# cm_ltc6102.net
KiCad netlist of a schematic drawn in EAGLE
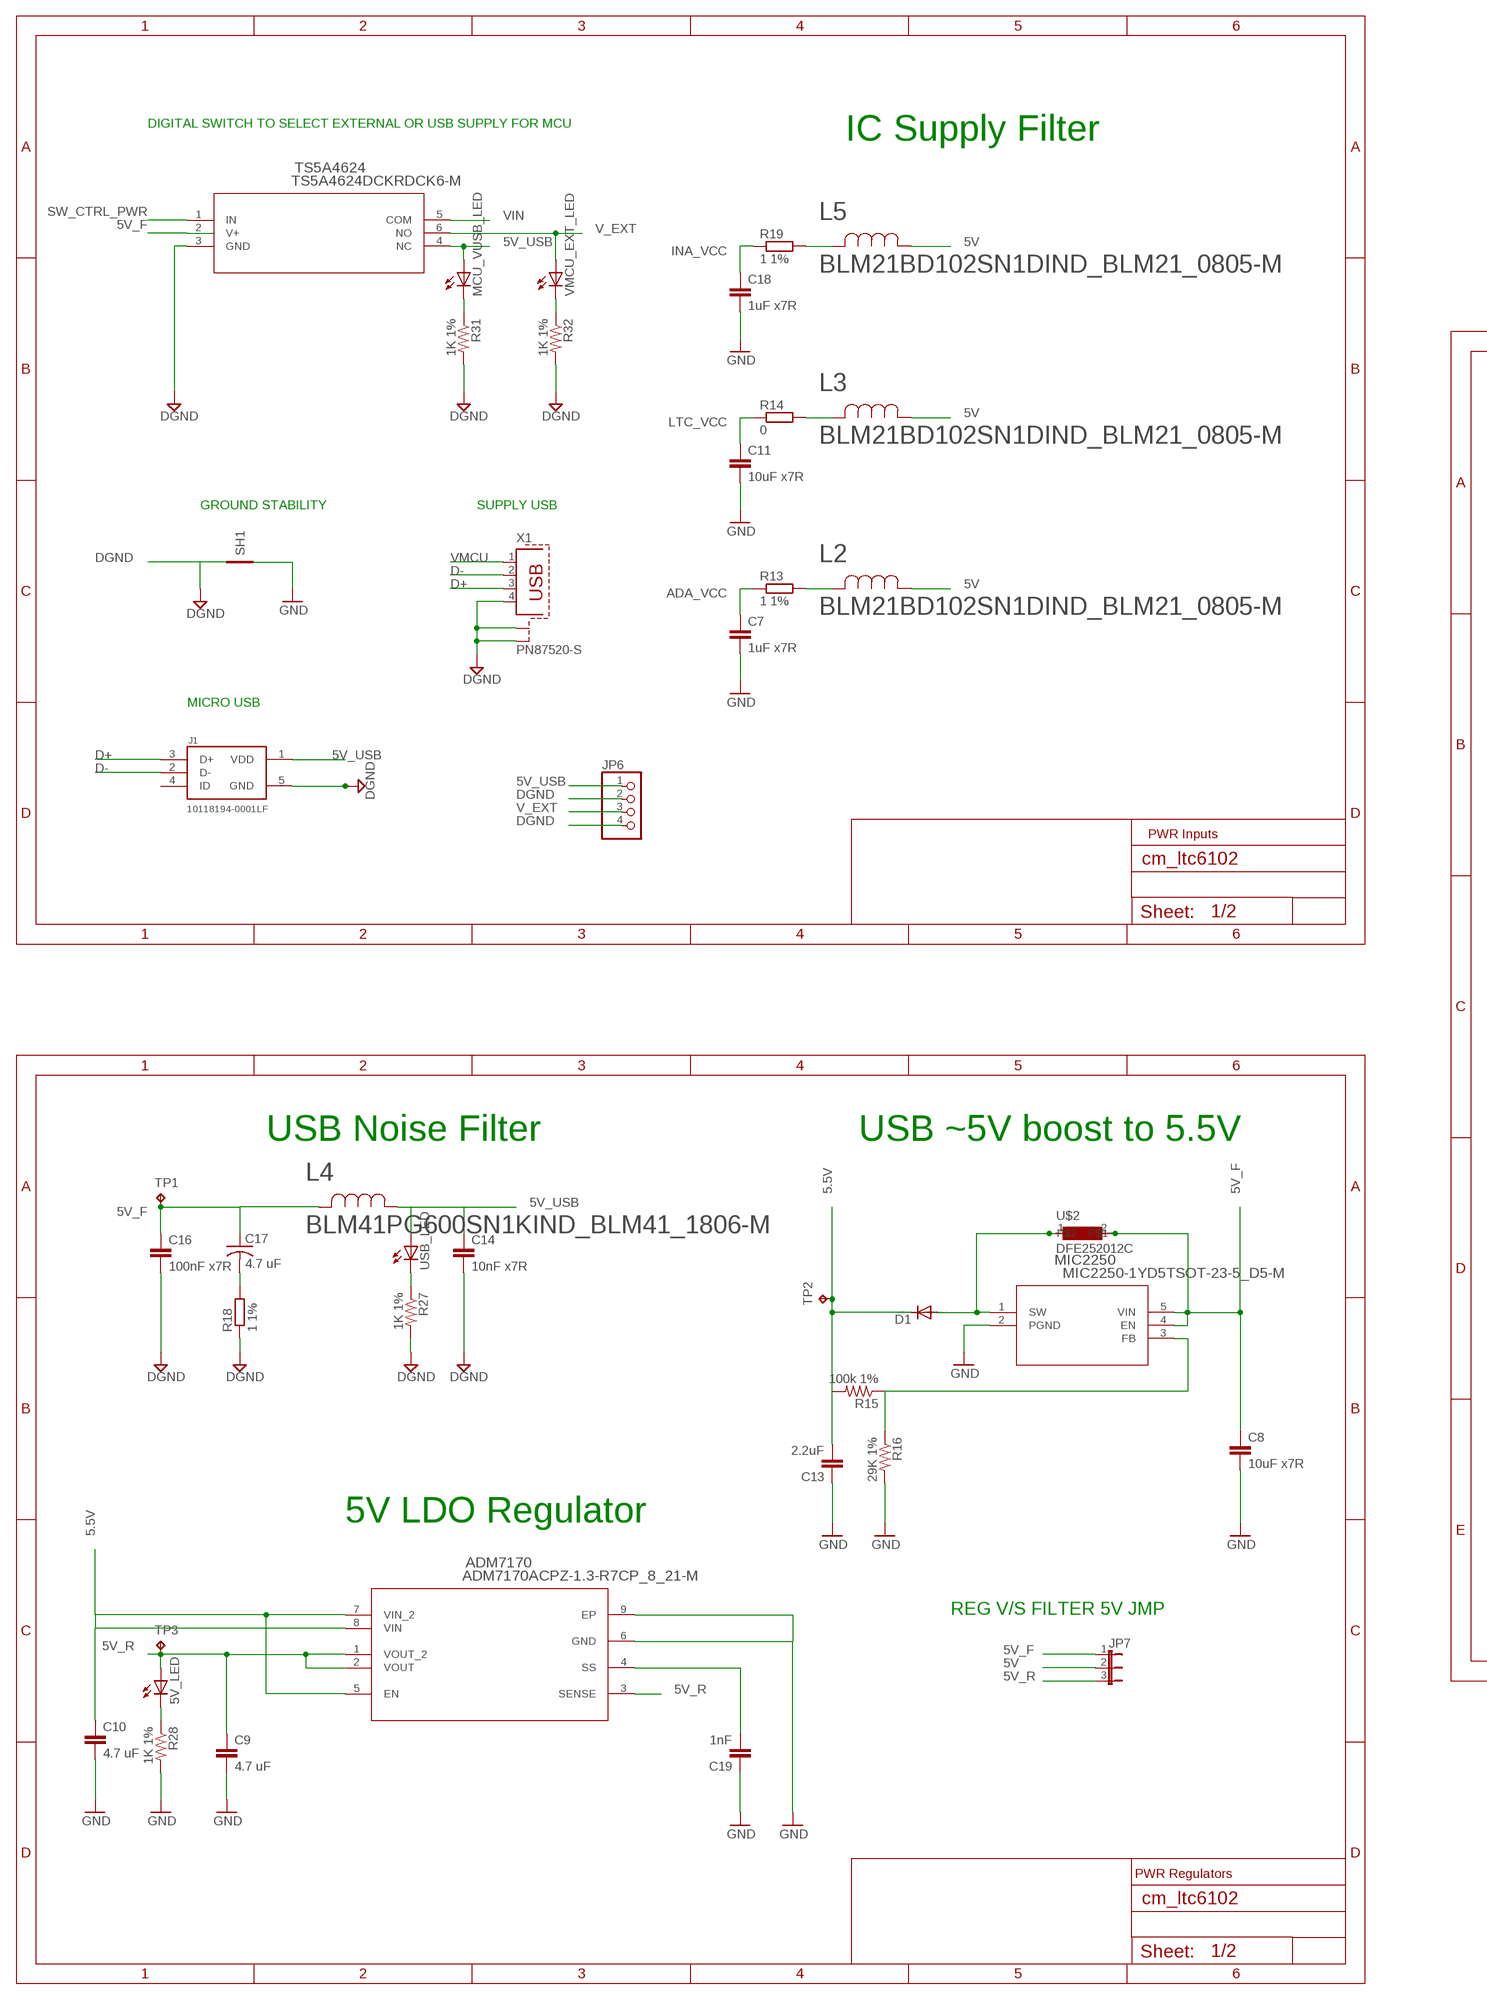
[diagram p0: schematic, sheet 1, part 1 of 2]
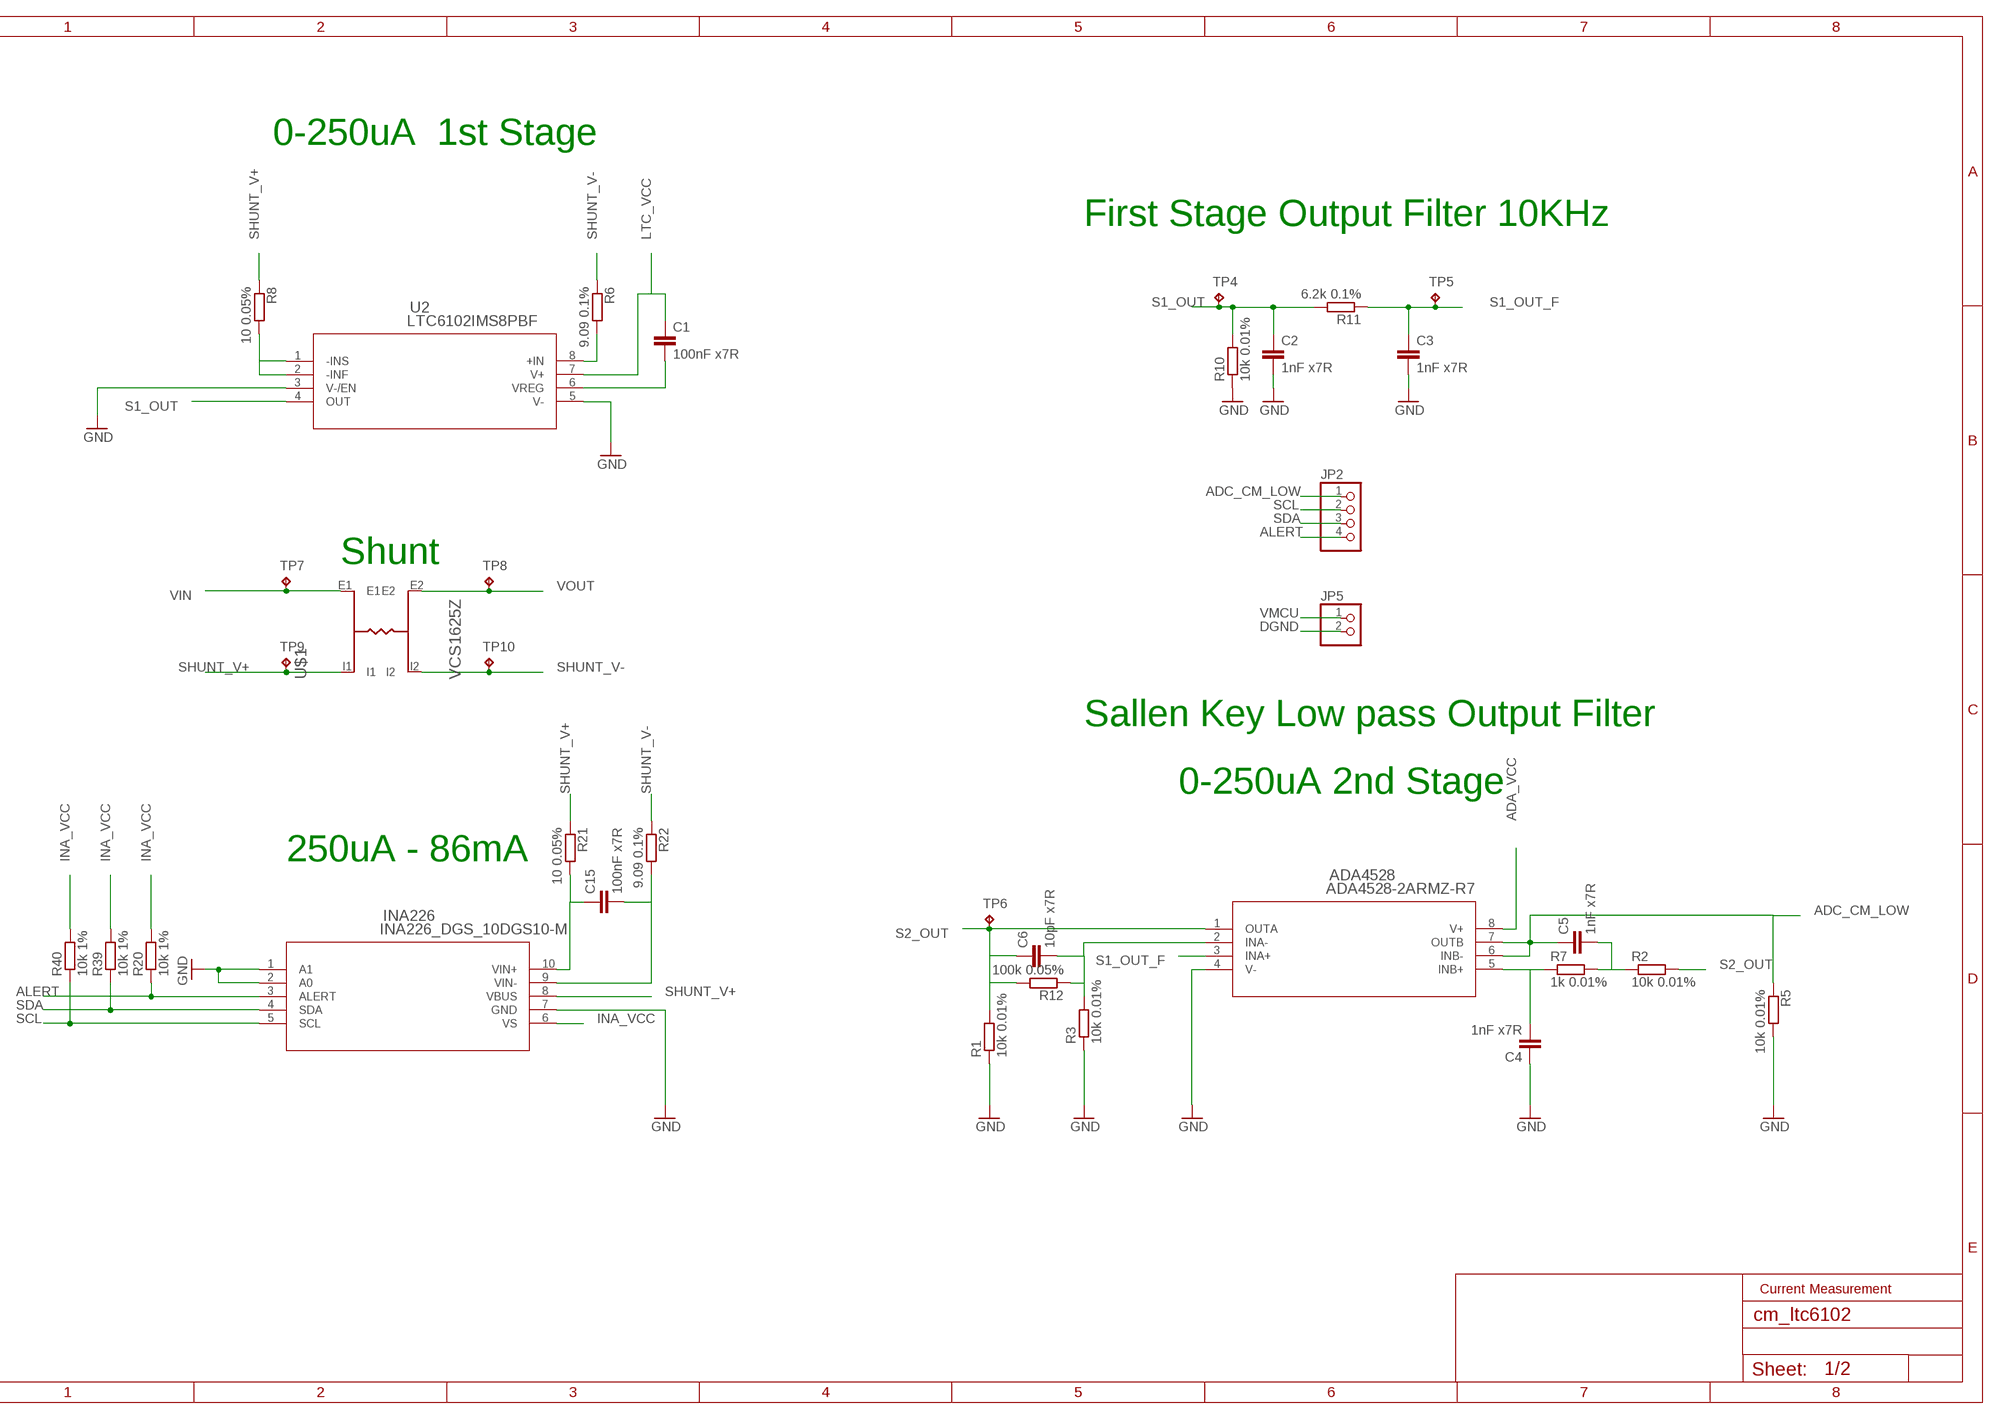
[diagram p1: schematic, sheet 1, part 2 of 2]
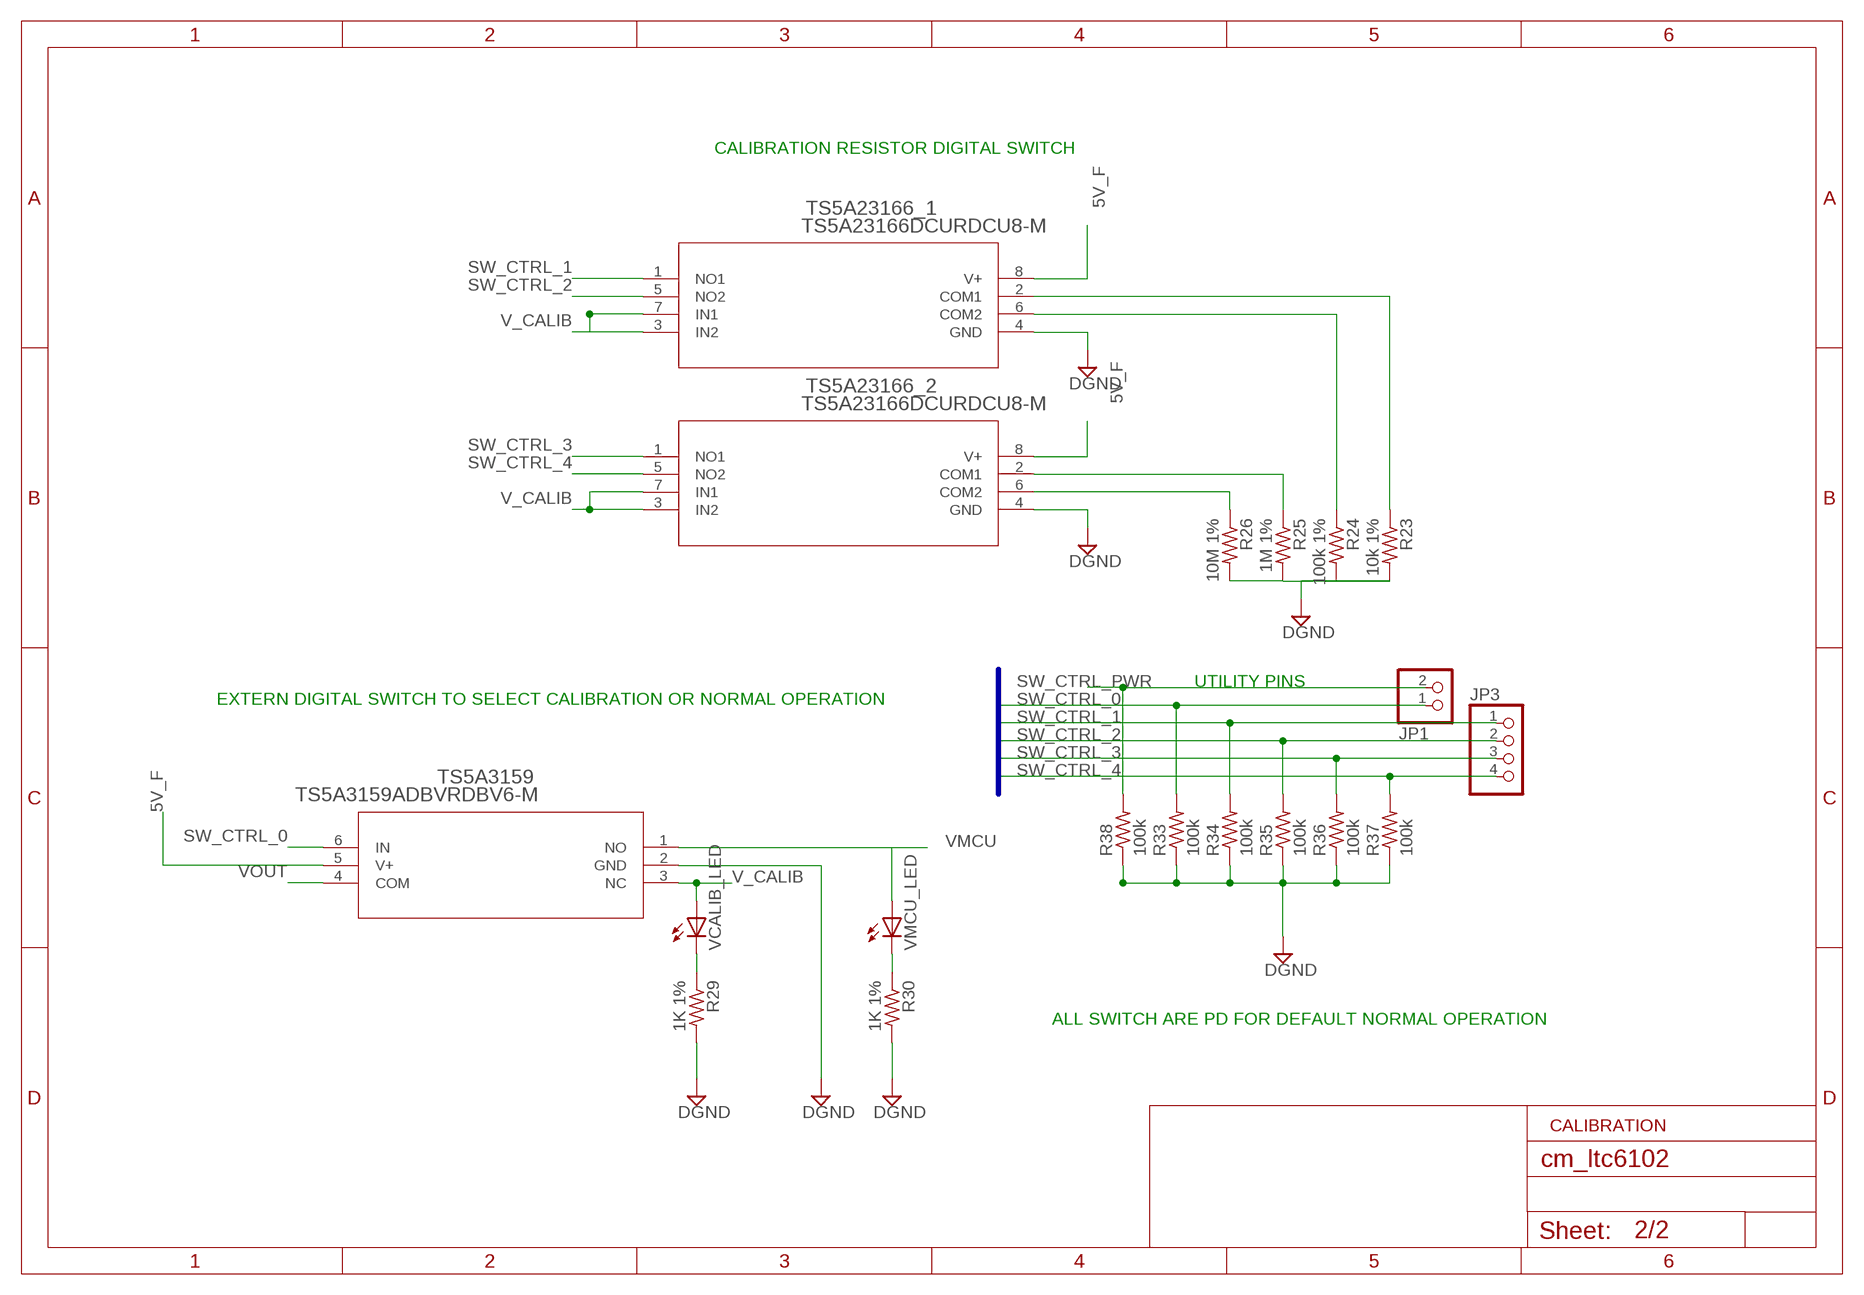
[diagram p2: schematic, sheet 2]

(export (version "E")
  (design (tool "Eeschema 10.0.6"))
  (components
    (comp (ref "5V_LED")
      (value "LEDCHIPLED_0603")
      (footprint "eagle-import:CHIPLED_0603")
      (libsource (lib "eagle-import") (part "LEDCHIPLED_0603"))
    )
    (comp (ref "ADA4528")
      (value "ADA4528-2ARMZ-R7")
      (footprint "eagle-import:RM_8")
      (fields (field (name "MANUFACTURER_PART_NUMBER") "ADA45282ARMZR7"))
      (libsource (lib "eagle-import") (part "ADA4528-2ARMZ-R7"))
    )
    (comp (ref "ADM7170")
      (value "ADM7170ACPZ-1.3-R7CP_8_21-M")
      (footprint "eagle-import:CP_8_21-M")
      (fields (field (name "MANUFACTURER_PART_NUMBER") "ADM7170ACPZ1.3R7"))
      (libsource (lib "eagle-import") (part "ADM7170ACPZ-1.3-R7CP_8_21-M"))
    )
    (comp (ref "C1")
      (value "100nF x7R")
      (footprint "eagle-import:C0603")
      (libsource (lib "eagle-import") (part "C-EUC0603"))
    )
    (comp (ref "C2")
      (value "1nF x7R")
      (footprint "eagle-import:C0603")
      (libsource (lib "eagle-import") (part "C-EUC0603"))
    )
    (comp (ref "C3")
      (value "1nF x7R")
      (footprint "eagle-import:C0603")
      (libsource (lib "eagle-import") (part "C-EUC0603"))
    )
    (comp (ref "C4")
      (value "1nF x7R")
      (footprint "eagle-import:C0603")
      (libsource (lib "eagle-import") (part "C-EUC0603"))
    )
    (comp (ref "C5")
      (value "1nF x7R")
      (footprint "eagle-import:C0603")
      (libsource (lib "eagle-import") (part "C-EUC0603"))
    )
    (comp (ref "C6")
      (value "10pF x7R")
      (footprint "eagle-import:C0603")
      (libsource (lib "eagle-import") (part "C-EUC0603"))
    )
    (comp (ref "C7")
      (value "1uF x7R")
      (footprint "eagle-import:C0603")
      (libsource (lib "eagle-import") (part "C-EUC0603"))
    )
    (comp (ref "C8")
      (value "10uF x7R")
      (footprint "eagle-import:C0805")
      (libsource (lib "eagle-import") (part "C-EUC0805"))
    )
    (comp (ref "C9")
      (value "4.7 uF")
      (footprint "eagle-import:C1206")
      (libsource (lib "eagle-import") (part "C-EUC1206"))
    )
    (comp (ref "C10")
      (value "4.7 uF")
      (footprint "eagle-import:C1206")
      (libsource (lib "eagle-import") (part "C-EUC1206"))
    )
    (comp (ref "C11")
      (value "10uF x7R")
      (footprint "eagle-import:C0805")
      (libsource (lib "eagle-import") (part "C-EUC0805"))
    )
    (comp (ref "C13")
      (value "2.2uF")
      (footprint "eagle-import:C0603")
      (libsource (lib "eagle-import") (part "C-EUC0603"))
    )
    (comp (ref "C14")
      (value "10nF x7R")
      (footprint "eagle-import:C0603")
      (libsource (lib "eagle-import") (part "C-EUC0603"))
    )
    (comp (ref "C15")
      (value "100nF x7R")
      (footprint "eagle-import:C0603")
      (libsource (lib "eagle-import") (part "C-EUC0603"))
    )
    (comp (ref "C16")
      (value "100nF x7R")
      (footprint "eagle-import:C0603")
      (libsource (lib "eagle-import") (part "C-EUC0603"))
    )
    (comp (ref "C17")
      (value "4.7 uF")
      (footprint "eagle-import:C1206")
      (libsource (lib "eagle-import") (part "C-USC1206"))
    )
    (comp (ref "C18")
      (value "1uF x7R")
      (footprint "eagle-import:C0603")
      (libsource (lib "eagle-import") (part "C-EUC0603"))
    )
    (comp (ref "C19")
      (value "1nF")
      (footprint "eagle-import:C0603")
      (libsource (lib "eagle-import") (part "C-EUC0603"))
    )
    (comp (ref "D1")
      (value "DIODE-SOD80C")
      (footprint "eagle-import:SOD80C")
      (libsource (lib "eagle-import") (part "DIODE-SOD80C"))
    )
    (comp (ref "INA226")
      (value "INA226_DGS_10DGS10-M")
      (footprint "eagle-import:DGS10-M")
      (fields (field (name "MANUFACTURER_PART_NUMBER") "INA226_DGS_10"))
      (libsource (lib "eagle-import") (part "INA226_DGS_10DGS10-M"))
    )
    (comp (ref "J1")
      (value "10118194-0001LF")
      (footprint "eagle-import:FRAMATOME_10118194-0001LF")
      (fields (field (name "MF") "Amphenol"))
      (libsource (lib "eagle-import") (part "10118194-0001LF"))
    )
    (comp (ref "JP2")
      (value "PINHD-1X4")
      (footprint "eagle-import:1X04")
      (libsource (lib "eagle-import") (part "PINHD-1X4"))
    )
    (comp (ref "JP5")
      (value "PINHD-1X2")
      (footprint "eagle-import:1X02")
      (libsource (lib "eagle-import") (part "PINHD-1X2"))
    )
    (comp (ref "JP6")
      (value "PINHD-1X4")
      (footprint "eagle-import:1X04")
      (libsource (lib "eagle-import") (part "PINHD-1X4"))
    )
    (comp (ref "JP7")
      (value "JP2E")
      (footprint "eagle-import:JP2")
      (libsource (lib "eagle-import") (part "JP2E"))
    )
    (comp (ref "L2")
      (value "BLM21BD102SN1DIND_BLM21_0805-M")
      (footprint "eagle-import:IND_BLM21_0805-M")
      (fields (field (name "MANUFACTURER_PART_NUMBER") "BLM21BD102SN1D"))
      (libsource (lib "eagle-import") (part "BLM21BD102SN1DIND_BLM21_0805-M"))
    )
    (comp (ref "L3")
      (value "BLM21BD102SN1DIND_BLM21_0805-M")
      (footprint "eagle-import:IND_BLM21_0805-M")
      (fields (field (name "MANUFACTURER_PART_NUMBER") "BLM21BD102SN1D"))
      (libsource (lib "eagle-import") (part "BLM21BD102SN1DIND_BLM21_0805-M"))
    )
    (comp (ref "L4")
      (value "BLM41PG600SN1KIND_BLM41_1806-M")
      (footprint "eagle-import:IND_BLM41_1806-M")
      (fields (field (name "MANUFACTURER_PART_NUMBER") "BLM41PG600SN1K"))
      (libsource (lib "eagle-import") (part "BLM41PG600SN1KIND_BLM41_1806-M"))
    )
    (comp (ref "L5")
      (value "BLM21BD102SN1DIND_BLM21_0805-M")
      (footprint "eagle-import:IND_BLM21_0805-M")
      (fields (field (name "MANUFACTURER_PART_NUMBER") "BLM21BD102SN1D"))
      (libsource (lib "eagle-import") (part "BLM21BD102SN1DIND_BLM21_0805-M"))
    )
    (comp (ref "MCU_VUSB_LED")
      (value "LEDCHIPLED_0603")
      (footprint "eagle-import:CHIPLED_0603")
      (libsource (lib "eagle-import") (part "LEDCHIPLED_0603"))
    )
    (comp (ref "MIC2250")
      (value "MIC2250-1YD5TSOT-23-5_D5-M")
      (footprint "eagle-import:TSOT-23-5_D5-M")
      (fields (field (name "MANUFACTURER_PART_NUMBER") "MIC22501YD5"))
      (libsource (lib "eagle-import") (part "MIC2250-1YD5TSOT-23-5_D5-M"))
    )
    (comp (ref "R1")
      (value "10k 0.01%")
      (footprint "eagle-import:R0603")
      (libsource (lib "eagle-import") (part "R-EU_R0603"))
    )
    (comp (ref "R2")
      (value "10k 0.01%")
      (footprint "eagle-import:R0603")
      (libsource (lib "eagle-import") (part "R-EU_R0603"))
    )
    (comp (ref "R3")
      (value "10k 0.01%")
      (footprint "eagle-import:R0603")
      (libsource (lib "eagle-import") (part "R-EU_R0603"))
    )
    (comp (ref "R5")
      (value "10k 0.01%")
      (footprint "eagle-import:R0603")
      (libsource (lib "eagle-import") (part "R-EU_R0603"))
    )
    (comp (ref "R6")
      (value "9.09 0.1%")
      (footprint "eagle-import:R0603")
      (libsource (lib "eagle-import") (part "R-EU_R0603"))
    )
    (comp (ref "R7")
      (value "1k 0.01%")
      (footprint "eagle-import:R0805")
      (libsource (lib "eagle-import") (part "R-EU_R0805"))
    )
    (comp (ref "R8")
      (value "10 0.05%")
      (footprint "eagle-import:R0603")
      (libsource (lib "eagle-import") (part "R-EU_R0603"))
    )
    (comp (ref "R10")
      (value "10k 0.01%")
      (footprint "eagle-import:R0603")
      (libsource (lib "eagle-import") (part "R-EU_R0603"))
    )
    (comp (ref "R11")
      (value "6.2k 0.1%")
      (footprint "eagle-import:R0603")
      (libsource (lib "eagle-import") (part "R-EU_R0603"))
    )
    (comp (ref "R12")
      (value "100k 0.05%")
      (footprint "eagle-import:R0603")
      (libsource (lib "eagle-import") (part "R-EU_R0603"))
    )
    (comp (ref "R13")
      (value "1 1%")
      (footprint "eagle-import:R0603")
      (libsource (lib "eagle-import") (part "R-EU_R0603"))
    )
    (comp (ref "R14")
      (value "0")
      (footprint "eagle-import:R0603")
      (libsource (lib "eagle-import") (part "R-EU_R0603"))
    )
    (comp (ref "R15")
      (value "100k 1%")
      (footprint "eagle-import:R0603")
      (libsource (lib "eagle-import") (part "R-US_R0603"))
    )
    (comp (ref "R16")
      (value "29K 1%")
      (footprint "eagle-import:R0603")
      (libsource (lib "eagle-import") (part "R-US_R0603"))
    )
    (comp (ref "R18")
      (value "1 1%")
      (footprint "eagle-import:R0603")
      (libsource (lib "eagle-import") (part "R-EU_R0603"))
    )
    (comp (ref "R19")
      (value "1 1%")
      (footprint "eagle-import:R0603")
      (libsource (lib "eagle-import") (part "R-EU_R0603"))
    )
    (comp (ref "R20")
      (value "10k 1%")
      (footprint "eagle-import:R0603")
      (libsource (lib "eagle-import") (part "R-EU_R0603"))
    )
    (comp (ref "R21")
      (value "10 0.05%")
      (footprint "eagle-import:R0603")
      (libsource (lib "eagle-import") (part "R-EU_R0603"))
    )
    (comp (ref "R22")
      (value "9.09 0.1%")
      (footprint "eagle-import:R0603")
      (libsource (lib "eagle-import") (part "R-EU_R0603"))
    )
    (comp (ref "R27")
      (value "1K 1%")
      (footprint "eagle-import:R0603")
      (libsource (lib "eagle-import") (part "R-US_R0603"))
    )
    (comp (ref "R28")
      (value "1K 1%")
      (footprint "eagle-import:R0603")
      (libsource (lib "eagle-import") (part "R-US_R0603"))
    )
    (comp (ref "R31")
      (value "1K 1%")
      (footprint "eagle-import:R0603")
      (libsource (lib "eagle-import") (part "R-US_R0603"))
    )
    (comp (ref "R32")
      (value "1K 1%")
      (footprint "eagle-import:R0603")
      (libsource (lib "eagle-import") (part "R-US_R0603"))
    )
    (comp (ref "R39")
      (value "10k 1%")
      (footprint "eagle-import:R0603")
      (libsource (lib "eagle-import") (part "R-EU_R0603"))
    )
    (comp (ref "R40")
      (value "10k 1%")
      (footprint "eagle-import:R0603")
      (libsource (lib "eagle-import") (part "R-EU_R0603"))
    )
    (comp (ref "SH1")
      (value "SHORT-VT5")
      (footprint "eagle-import:SHORT_TOP-50")
      (libsource (lib "eagle-import") (part "SHORT-VT5"))
    )
    (comp (ref "TP1")
      (value "TPPAD1-20")
      (footprint "eagle-import:P1-20")
      (libsource (lib "eagle-import") (part "TPPAD1-20"))
    )
    (comp (ref "TP2")
      (value "TPPAD1-20")
      (footprint "eagle-import:P1-20")
      (libsource (lib "eagle-import") (part "TPPAD1-20"))
    )
    (comp (ref "TP3")
      (value "TPPAD1-20")
      (footprint "eagle-import:P1-20")
      (libsource (lib "eagle-import") (part "TPPAD1-20"))
    )
    (comp (ref "TP4")
      (value "TPPAD1-20")
      (footprint "eagle-import:P1-20")
      (libsource (lib "eagle-import") (part "TPPAD1-20"))
    )
    (comp (ref "TP5")
      (value "TPPAD1-20")
      (footprint "eagle-import:P1-20")
      (libsource (lib "eagle-import") (part "TPPAD1-20"))
    )
    (comp (ref "TP6")
      (value "TPPAD1-20")
      (footprint "eagle-import:P1-20")
      (libsource (lib "eagle-import") (part "TPPAD1-20"))
    )
    (comp (ref "TP7")
      (value "TPPAD1-20")
      (footprint "eagle-import:P1-20")
      (libsource (lib "eagle-import") (part "TPPAD1-20"))
    )
    (comp (ref "TP8")
      (value "TPPAD1-20")
      (footprint "eagle-import:P1-20")
      (libsource (lib "eagle-import") (part "TPPAD1-20"))
    )
    (comp (ref "TP9")
      (value "TPPAD1-20")
      (footprint "eagle-import:P1-20")
      (libsource (lib "eagle-import") (part "TPPAD1-20"))
    )
    (comp (ref "TP10")
      (value "TPPAD1-20")
      (footprint "eagle-import:P1-20")
      (libsource (lib "eagle-import") (part "TPPAD1-20"))
    )
    (comp (ref "TS5A4624")
      (value "TS5A4624DCKRDCK6-M")
      (footprint "eagle-import:DCK6-M")
      (fields (field (name "MANUFACTURER_PART_NUMBER") "TS5A4624DCKR"))
      (libsource (lib "eagle-import") (part "TS5A4624DCKRDCK6-M"))
    )
    (comp (ref "U$1")
      (value "VCS1625Z")
      (footprint "eagle-import:VCS1625Z")
      (libsource (lib "eagle-import") (part "VCS1625Z"))
    )
    (comp (ref "U$2")
      (value "DFE252012C")
      (footprint "eagle-import:DFE252012C")
      (libsource (lib "eagle-import") (part "DFE252012C"))
    )
    (comp (ref "U2")
      (value "LTC6102IMS8PBF")
      (footprint "eagle-import:MSOP-8_MS")
      (fields (field (name "MANUFACTURER_PART_NUMBER") "LTC6102IMS8#PBF"))
      (libsource (lib "eagle-import") (part "LTC6102IMS8PBF"))
    )
    (comp (ref "USB_LED")
      (value "LEDCHIPLED_0603")
      (footprint "eagle-import:CHIPLED_0603")
      (libsource (lib "eagle-import") (part "LEDCHIPLED_0603"))
    )
    (comp (ref "VMCU_EXT_LED")
      (value "LEDCHIPLED_0603")
      (footprint "eagle-import:CHIPLED_0603")
      (libsource (lib "eagle-import") (part "LEDCHIPLED_0603"))
    )
    (comp (ref "X1")
      (value "PN87520-S")
      (footprint "eagle-import:PN87520-S")
      (libsource (lib "eagle-import") (part "PN87520-S"))
    )
    (comp (ref "JP1")
      (value "PINHD-1X2")
      (footprint "eagle-import:1X02")
      (libsource (lib "eagle-import") (part "PINHD-1X2"))
    )
    (comp (ref "JP3")
      (value "PINHD-1X4")
      (footprint "eagle-import:1X04")
      (libsource (lib "eagle-import") (part "PINHD-1X4"))
    )
    (comp (ref "R23")
      (value "10k 1%")
      (footprint "eagle-import:R0603")
      (libsource (lib "eagle-import") (part "R-US_R0603"))
    )
    (comp (ref "R24")
      (value "100k 1%")
      (footprint "eagle-import:R0603")
      (libsource (lib "eagle-import") (part "R-US_R0603"))
    )
    (comp (ref "R25")
      (value "1M 1%")
      (footprint "eagle-import:R0603")
      (libsource (lib "eagle-import") (part "R-US_R0603"))
    )
    (comp (ref "R26")
      (value "10M 1%")
      (footprint "eagle-import:R0603")
      (libsource (lib "eagle-import") (part "R-US_R0603"))
    )
    (comp (ref "R29")
      (value "1K 1%")
      (footprint "eagle-import:R0603")
      (libsource (lib "eagle-import") (part "R-US_R0603"))
    )
    (comp (ref "R30")
      (value "1K 1%")
      (footprint "eagle-import:R0603")
      (libsource (lib "eagle-import") (part "R-US_R0603"))
    )
    (comp (ref "R33")
      (value "100k")
      (footprint "eagle-import:R0805")
      (libsource (lib "eagle-import") (part "resistor_348_R-US_R0805"))
    )
    (comp (ref "R34")
      (value "100k")
      (footprint "eagle-import:R0805")
      (libsource (lib "eagle-import") (part "resistor_348_R-US_R0805"))
    )
    (comp (ref "R35")
      (value "100k")
      (footprint "eagle-import:R0805")
      (libsource (lib "eagle-import") (part "resistor_348_R-US_R0805"))
    )
    (comp (ref "R36")
      (value "100k")
      (footprint "eagle-import:R0805")
      (libsource (lib "eagle-import") (part "resistor_348_R-US_R0805"))
    )
    (comp (ref "R37")
      (value "100k")
      (footprint "eagle-import:R0805")
      (libsource (lib "eagle-import") (part "resistor_348_R-US_R0805"))
    )
    (comp (ref "R38")
      (value "100k")
      (footprint "eagle-import:R0805")
      (libsource (lib "eagle-import") (part "resistor_348_R-US_R0805"))
    )
    (comp (ref "TS5A3159")
      (value "TS5A3159ADBVRDBV6-M")
      (footprint "eagle-import:DBV6-M")
      (fields (field (name "MANUFACTURER_PART_NUMBER") "TS5A3159ADBVR"))
      (libsource (lib "eagle-import") (part "TS5A3159ADBVRDBV6-M"))
    )
    (comp (ref "TS5A23166_1")
      (value "TS5A23166DCURDCU8-M")
      (footprint "eagle-import:DCU8-M")
      (fields (field (name "MANUFACTURER_PART_NUMBER") "TS5A23166DCUR"))
      (libsource (lib "eagle-import") (part "TS5A23166DCURDCU8-M"))
    )
    (comp (ref "TS5A23166_2")
      (value "TS5A23166DCURDCU8-M")
      (footprint "eagle-import:DCU8-M")
      (fields (field (name "MANUFACTURER_PART_NUMBER") "TS5A23166DCUR"))
      (libsource (lib "eagle-import") (part "TS5A23166DCURDCU8-M"))
    )
    (comp (ref "VCALIB_LED")
      (value "LEDCHIPLED_0603")
      (footprint "eagle-import:CHIPLED_0603")
      (libsource (lib "eagle-import") (part "LEDCHIPLED_0603"))
    )
    (comp (ref "VMCU_LED")
      (value "LEDCHIPLED_0603")
      (footprint "eagle-import:CHIPLED_0603")
      (libsource (lib "eagle-import") (part "LEDCHIPLED_0603"))
    )
  )
  (nets
    (net (code "1") (name "5.5V") (class "Default")
      (node (ref "ADM7170") (pin "5") (pinfunction "EN_5") (pintype "passive"))
      (node (ref "ADM7170") (pin "7") (pinfunction "VIN_2_7") (pintype "passive"))
      (node (ref "ADM7170") (pin "8") (pinfunction "VIN_8") (pintype "passive"))
      (node (ref "C10") (pin "1") (pinfunction "1_1") (pintype "passive"))
      (node (ref "C13") (pin "2") (pinfunction "2_2") (pintype "passive"))
      (node (ref "D1") (pin "C") (pinfunction "C_C") (pintype "passive"))
      (node (ref "R15") (pin "2") (pinfunction "2_2") (pintype "passive"))
      (node (ref "TP2") (pin "TP") (pinfunction "TP_TP") (pintype "input"))
    )
    (net (code "2") (name "5V") (class "Default")
      (node (ref "JP7") (pin "2") (pinfunction "2_2") (pintype "passive"))
      (node (ref "L2") (pin "1") (pinfunction "1_1") (pintype "passive"))
      (node (ref "L3") (pin "1") (pinfunction "1_1") (pintype "passive"))
      (node (ref "L5") (pin "1") (pinfunction "1_1") (pintype "passive"))
    )
    (net (code "3") (name "5V_F") (class "Default")
      (node (ref "C16") (pin "1") (pinfunction "1_1") (pintype "passive"))
      (node (ref "C17") (pin "1") (pinfunction "1_1") (pintype "passive"))
      (node (ref "C8") (pin "1") (pinfunction "1_1") (pintype "passive"))
      (node (ref "JP7") (pin "1") (pinfunction "1_1") (pintype "passive"))
      (node (ref "L4") (pin "2") (pinfunction "2_2") (pintype "passive"))
      (node (ref "MIC2250") (pin "4") (pinfunction "EN_4") (pintype "input"))
      (node (ref "MIC2250") (pin "5") (pinfunction "VIN_5") (pintype "input"))
      (node (ref "TP1") (pin "TP") (pinfunction "TP_TP") (pintype "input"))
      (node (ref "TS5A23166_1") (pin "8") (pinfunction "V+_8") (pintype "passive"))
      (node (ref "TS5A23166_2") (pin "8") (pinfunction "V+_8") (pintype "passive"))
      (node (ref "TS5A3159") (pin "5") (pinfunction "V+_5") (pintype "power_in"))
      (node (ref "TS5A4624") (pin "2") (pinfunction "V+_2") (pintype "power_in"))
      (node (ref "U$2") (pin "2") (pinfunction "P$2_2") (pintype "bidirectional"))
    )
    (net (code "4") (name "5V_R") (class "Default")
      (node (ref "5V_LED") (pin "A") (pinfunction "A_A") (pintype "passive"))
      (node (ref "ADM7170") (pin "1") (pinfunction "VOUT_2_1") (pintype "passive"))
      (node (ref "ADM7170") (pin "2") (pinfunction "VOUT_2") (pintype "passive"))
      (node (ref "ADM7170") (pin "3") (pinfunction "SENSE_3") (pintype "passive"))
      (node (ref "C9") (pin "1") (pinfunction "1_1") (pintype "passive"))
      (node (ref "JP7") (pin "3") (pinfunction "3_3") (pintype "passive"))
      (node (ref "TP3") (pin "TP") (pinfunction "TP_TP") (pintype "input"))
    )
    (net (code "5") (name "5V_USB") (class "Default")
      (node (ref "C14") (pin "1") (pinfunction "1_1") (pintype "passive"))
      (node (ref "J1") (pin "1") (pinfunction "VDD_1") (pintype "power_in"))
      (node (ref "JP6") (pin "1") (pinfunction "1_1") (pintype "passive"))
      (node (ref "L4") (pin "1") (pinfunction "1_1") (pintype "passive"))
      (node (ref "MCU_VUSB_LED") (pin "A") (pinfunction "A_A") (pintype "passive"))
      (node (ref "TS5A4624") (pin "4") (pinfunction "NC_4") (pintype "passive"))
      (node (ref "USB_LED") (pin "A") (pinfunction "A_A") (pintype "passive"))
    )
    (net (code "6") (name "ADA_VCC") (class "Default")
      (node (ref "ADA4528") (pin "8") (pinfunction "V+_8") (pintype "power_in"))
      (node (ref "C7") (pin "1") (pinfunction "1_1") (pintype "passive"))
      (node (ref "R13") (pin "1") (pinfunction "1_1") (pintype "passive"))
    )
    (net (code "7") (name "ADC_CM_LOW") (class "Default")
      (node (ref "ADA4528") (pin "6") (pinfunction "INB-_6") (pintype "input"))
      (node (ref "ADA4528") (pin "7") (pinfunction "OUTB_7") (pintype "output"))
      (node (ref "C5") (pin "1") (pinfunction "1_1") (pintype "passive"))
      (node (ref "JP2") (pin "1") (pinfunction "1_1") (pintype "passive"))
      (node (ref "R5") (pin "1") (pinfunction "1_1") (pintype "passive"))
    )
    (net (code "8") (name "ALERT") (class "Default")
      (node (ref "INA226") (pin "3") (pinfunction "ALERT_3") (pintype "output"))
      (node (ref "JP2") (pin "4") (pinfunction "4_4") (pintype "passive"))
      (node (ref "R20") (pin "1") (pinfunction "1_1") (pintype "passive"))
    )
    (net (code "9") (name "D+") (class "Default")
      (node (ref "J1") (pin "3") (pinfunction "D+_3") (pintype "bidirectional"))
      (node (ref "X1") (pin "3") (pinfunction "3_3") (pintype "passive"))
    )
    (net (code "10") (name "D-") (class "Default")
      (node (ref "J1") (pin "2") (pinfunction "D-_2") (pintype "bidirectional"))
      (node (ref "X1") (pin "2") (pinfunction "2_2") (pintype "passive"))
    )
    (net (code "11") (name "DGND") (class "Default")
      (node (ref "C14") (pin "2") (pinfunction "2_2") (pintype "passive"))
      (node (ref "C16") (pin "2") (pinfunction "2_2") (pintype "passive"))
      (node (ref "J1") (pin "5") (pinfunction "GND_5") (pintype "power_in"))
      (node (ref "JP5") (pin "2") (pinfunction "2_2") (pintype "passive"))
      (node (ref "JP6") (pin "2") (pinfunction "2_2") (pintype "passive"))
      (node (ref "JP6") (pin "4") (pinfunction "4_4") (pintype "passive"))
      (node (ref "R18") (pin "1") (pinfunction "1_1") (pintype "passive"))
      (node (ref "R23") (pin "2") (pinfunction "2_2") (pintype "passive"))
      (node (ref "R24") (pin "2") (pinfunction "2_2") (pintype "passive"))
      (node (ref "R25") (pin "2") (pinfunction "2_2") (pintype "passive"))
      (node (ref "R26") (pin "2") (pinfunction "2_2") (pintype "passive"))
      (node (ref "R27") (pin "2") (pinfunction "2_2") (pintype "passive"))
      (node (ref "R29") (pin "2") (pinfunction "2_2") (pintype "passive"))
      (node (ref "R30") (pin "2") (pinfunction "2_2") (pintype "passive"))
      (node (ref "R31") (pin "2") (pinfunction "2_2") (pintype "passive"))
      (node (ref "R32") (pin "2") (pinfunction "2_2") (pintype "passive"))
      (node (ref "R33") (pin "1") (pinfunction "1_1") (pintype "passive"))
      (node (ref "R34") (pin "1") (pinfunction "1_1") (pintype "passive"))
      (node (ref "R35") (pin "1") (pinfunction "1_1") (pintype "passive"))
      (node (ref "R36") (pin "1") (pinfunction "1_1") (pintype "passive"))
      (node (ref "R37") (pin "1") (pinfunction "1_1") (pintype "passive"))
      (node (ref "R38") (pin "1") (pinfunction "1_1") (pintype "passive"))
      (node (ref "SH1") (pin "2") (pinfunction "P$2_2") (pintype "bidirectional"))
      (node (ref "TS5A23166_1") (pin "4") (pinfunction "GND_4") (pintype "power_in"))
      (node (ref "TS5A23166_2") (pin "4") (pinfunction "GND_4") (pintype "power_in"))
      (node (ref "TS5A3159") (pin "2") (pinfunction "GND_2") (pintype "power_in"))
      (node (ref "TS5A4624") (pin "3") (pinfunction "GND_3") (pintype "power_in"))
      (node (ref "X1") (pin "4") (pinfunction "4_4") (pintype "passive"))
      (node (ref "X1") (pin "S1") (pinfunction "S1_S1") (pintype "passive"))
      (node (ref "X1") (pin "S2") (pinfunction "S2_S2") (pintype "passive"))
    )
    (net (code "12") (name "GND") (class "Default")
      (node (ref "ADA4528") (pin "4") (pinfunction "V-_4") (pintype "power_in"))
      (node (ref "ADM7170") (pin "6") (pinfunction "GND_6") (pintype "passive"))
      (node (ref "ADM7170") (pin "9") (pinfunction "EP_9") (pintype "passive"))
      (node (ref "C10") (pin "2") (pinfunction "2_2") (pintype "passive"))
      (node (ref "C11") (pin "2") (pinfunction "2_2") (pintype "passive"))
      (node (ref "C13") (pin "1") (pinfunction "1_1") (pintype "passive"))
      (node (ref "C18") (pin "2") (pinfunction "2_2") (pintype "passive"))
      (node (ref "C19") (pin "1") (pinfunction "1_1") (pintype "passive"))
      (node (ref "C2") (pin "2") (pinfunction "2_2") (pintype "passive"))
      (node (ref "C3") (pin "2") (pinfunction "2_2") (pintype "passive"))
      (node (ref "C4") (pin "1") (pinfunction "1_1") (pintype "passive"))
      (node (ref "C7") (pin "2") (pinfunction "2_2") (pintype "passive"))
      (node (ref "C8") (pin "2") (pinfunction "2_2") (pintype "passive"))
      (node (ref "C9") (pin "2") (pinfunction "2_2") (pintype "passive"))
      (node (ref "INA226") (pin "1") (pinfunction "A1_1") (pintype "passive"))
      (node (ref "INA226") (pin "2") (pinfunction "A0_2") (pintype "passive"))
      (node (ref "INA226") (pin "7") (pinfunction "GND_7") (pintype "power_in"))
      (node (ref "MIC2250") (pin "2") (pinfunction "PGND_2") (pintype "power_in"))
      (node (ref "R1") (pin "1") (pinfunction "1_1") (pintype "passive"))
      (node (ref "R10") (pin "1") (pinfunction "1_1") (pintype "passive"))
      (node (ref "R16") (pin "2") (pinfunction "2_2") (pintype "passive"))
      (node (ref "R28") (pin "2") (pinfunction "2_2") (pintype "passive"))
      (node (ref "R3") (pin "1") (pinfunction "1_1") (pintype "passive"))
      (node (ref "R5") (pin "2") (pinfunction "2_2") (pintype "passive"))
      (node (ref "SH1") (pin "1") (pinfunction "P$1_1") (pintype "bidirectional"))
      (node (ref "U2") (pin "3") (pinfunction "V-/EN_3") (pintype "bidirectional"))
      (node (ref "U2") (pin "5") (pinfunction "V-_5") (pintype "power_in"))
    )
    (net (code "13") (name "INA_VCC") (class "Default")
      (node (ref "C18") (pin "1") (pinfunction "1_1") (pintype "passive"))
      (node (ref "INA226") (pin "6") (pinfunction "VS_6") (pintype "power_in"))
      (node (ref "R19") (pin "1") (pinfunction "1_1") (pintype "passive"))
      (node (ref "R20") (pin "2") (pinfunction "2_2") (pintype "passive"))
      (node (ref "R39") (pin "2") (pinfunction "2_2") (pintype "passive"))
      (node (ref "R40") (pin "2") (pinfunction "2_2") (pintype "passive"))
    )
    (net (code "14") (name "LTC_VCC") (class "Default")
      (node (ref "C1") (pin "1") (pinfunction "1_1") (pintype "passive"))
      (node (ref "C11") (pin "1") (pinfunction "1_1") (pintype "passive"))
      (node (ref "R14") (pin "1") (pinfunction "1_1") (pintype "passive"))
      (node (ref "U2") (pin "7") (pinfunction "V+_7") (pintype "power_in"))
    )
    (net (code "15") (name "Net-(5V_LED-PadC)") (class "Default")
      (node (ref "5V_LED") (pin "C") (pinfunction "C_C") (pintype "passive"))
      (node (ref "R28") (pin "1") (pinfunction "1_1") (pintype "passive"))
    )
    (net (code "16") (name "Net-(ADA4528-INA-)") (class "Default")
      (node (ref "ADA4528") (pin "2") (pinfunction "INA-_2") (pintype "input"))
      (node (ref "C6") (pin "2") (pinfunction "2_2") (pintype "passive"))
      (node (ref "R12") (pin "1") (pinfunction "1_1") (pintype "passive"))
      (node (ref "R3") (pin "2") (pinfunction "2_2") (pintype "passive"))
    )
    (net (code "17") (name "Net-(ADA4528-INB+)") (class "Default")
      (node (ref "ADA4528") (pin "5") (pinfunction "INB+_5") (pintype "input"))
      (node (ref "C4") (pin "2") (pinfunction "2_2") (pintype "passive"))
      (node (ref "R7") (pin "1") (pinfunction "1_1") (pintype "passive"))
    )
    (net (code "18") (name "Net-(ADM7170-SS)") (class "Default")
      (node (ref "ADM7170") (pin "4") (pinfunction "SS_4") (pintype "passive"))
      (node (ref "C19") (pin "2") (pinfunction "2_2") (pintype "passive"))
    )
    (net (code "19") (name "Net-(C5-Pad2)") (class "Default")
      (node (ref "C5") (pin "2") (pinfunction "2_2") (pintype "passive"))
      (node (ref "R2") (pin "1") (pinfunction "1_1") (pintype "passive"))
      (node (ref "R7") (pin "2") (pinfunction "2_2") (pintype "passive"))
    )
    (net (code "20") (name "Net-(C17-Pad2)") (class "Default")
      (node (ref "C17") (pin "2") (pinfunction "2_2") (pintype "passive"))
      (node (ref "R18") (pin "2") (pinfunction "2_2") (pintype "passive"))
    )
    (net (code "21") (name "Net-(INA226-VIN+)") (class "Default")
      (node (ref "C15") (pin "1") (pinfunction "1_1") (pintype "passive"))
      (node (ref "INA226") (pin "10") (pinfunction "VIN+_10") (pintype "input"))
      (node (ref "R21") (pin "2") (pinfunction "2_2") (pintype "passive"))
    )
    (net (code "22") (name "Net-(INA226-VIN-)") (class "Default")
      (node (ref "C15") (pin "2") (pinfunction "2_2") (pintype "passive"))
      (node (ref "INA226") (pin "9") (pinfunction "VIN-_9") (pintype "input"))
      (node (ref "R22") (pin "2") (pinfunction "2_2") (pintype "passive"))
    )
    (net (code "23") (name "Net-(L2-Pad2)") (class "Default")
      (node (ref "L2") (pin "2") (pinfunction "2_2") (pintype "passive"))
      (node (ref "R13") (pin "2") (pinfunction "2_2") (pintype "passive"))
    )
    (net (code "24") (name "Net-(L3-Pad2)") (class "Default")
      (node (ref "L3") (pin "2") (pinfunction "2_2") (pintype "passive"))
      (node (ref "R14") (pin "2") (pinfunction "2_2") (pintype "passive"))
    )
    (net (code "25") (name "Net-(L5-Pad2)") (class "Default")
      (node (ref "L5") (pin "2") (pinfunction "2_2") (pintype "passive"))
      (node (ref "R19") (pin "2") (pinfunction "2_2") (pintype "passive"))
    )
    (net (code "26") (name "Net-(MCU_VUSB_LED-PadC)") (class "Default")
      (node (ref "MCU_VUSB_LED") (pin "C") (pinfunction "C_C") (pintype "passive"))
      (node (ref "R31") (pin "1") (pinfunction "1_1") (pintype "passive"))
    )
    (net (code "27") (name "Net-(MIC2250-FB)") (class "Default")
      (node (ref "MIC2250") (pin "3") (pinfunction "FB_3") (pintype "input"))
      (node (ref "R15") (pin "1") (pinfunction "1_1") (pintype "passive"))
      (node (ref "R16") (pin "1") (pinfunction "1_1") (pintype "passive"))
    )
    (net (code "28") (name "Net-(MIC2250-SW)") (class "Default")
      (node (ref "D1") (pin "A") (pinfunction "A_A") (pintype "passive"))
      (node (ref "MIC2250") (pin "1") (pinfunction "SW_1") (pintype "input"))
      (node (ref "U$2") (pin "1") (pinfunction "P$1_1") (pintype "bidirectional"))
    )
    (net (code "29") (name "Net-(R27-Pad1)") (class "Default")
      (node (ref "R27") (pin "1") (pinfunction "1_1") (pintype "passive"))
      (node (ref "USB_LED") (pin "C") (pinfunction "C_C") (pintype "passive"))
    )
    (net (code "30") (name "Net-(R29-Pad1)") (class "Default")
      (node (ref "R29") (pin "1") (pinfunction "1_1") (pintype "passive"))
      (node (ref "VCALIB_LED") (pin "C") (pinfunction "C_C") (pintype "passive"))
    )
    (net (code "31") (name "Net-(R30-Pad1)") (class "Default")
      (node (ref "R30") (pin "1") (pinfunction "1_1") (pintype "passive"))
      (node (ref "VMCU_LED") (pin "C") (pinfunction "C_C") (pintype "passive"))
    )
    (net (code "32") (name "Net-(R32-Pad1)") (class "Default")
      (node (ref "R32") (pin "1") (pinfunction "1_1") (pintype "passive"))
      (node (ref "VMCU_EXT_LED") (pin "C") (pinfunction "C_C") (pintype "passive"))
    )
    (net (code "33") (name "Net-(TS5A23166_1-COM1)") (class "Default")
      (node (ref "R23") (pin "1") (pinfunction "1_1") (pintype "passive"))
      (node (ref "TS5A23166_1") (pin "2") (pinfunction "COM1_2") (pintype "passive"))
    )
    (net (code "34") (name "Net-(TS5A23166_1-COM2)") (class "Default")
      (node (ref "R24") (pin "1") (pinfunction "1_1") (pintype "passive"))
      (node (ref "TS5A23166_1") (pin "6") (pinfunction "COM2_6") (pintype "passive"))
    )
    (net (code "35") (name "Net-(TS5A23166_2-COM1)") (class "Default")
      (node (ref "R25") (pin "1") (pinfunction "1_1") (pintype "passive"))
      (node (ref "TS5A23166_2") (pin "2") (pinfunction "COM1_2") (pintype "passive"))
    )
    (net (code "36") (name "Net-(TS5A23166_2-COM2)") (class "Default")
      (node (ref "R26") (pin "1") (pinfunction "1_1") (pintype "passive"))
      (node (ref "TS5A23166_2") (pin "6") (pinfunction "COM2_6") (pintype "passive"))
    )
    (net (code "37") (name "Net-(U2-+IN)") (class "Default")
      (node (ref "R6") (pin "2") (pinfunction "2_2") (pintype "passive"))
      (node (ref "U2") (pin "8") (pinfunction "+IN_8") (pintype "input"))
    )
    (net (code "38") (name "Net-(U2--INF)") (class "Default")
      (node (ref "R8") (pin "2") (pinfunction "2_2") (pintype "passive"))
      (node (ref "U2") (pin "1") (pinfunction "-INS_1") (pintype "input"))
      (node (ref "U2") (pin "2") (pinfunction "-INF_2") (pintype "input"))
    )
    (net (code "39") (name "Net-(U2-VREG)") (class "Default")
      (node (ref "C1") (pin "2") (pinfunction "2_2") (pintype "passive"))
      (node (ref "U2") (pin "6") (pinfunction "VREG_6") (pintype "passive"))
    )
    (net (code "40") (name "S1_OUT") (class "Default")
      (node (ref "C2") (pin "1") (pinfunction "1_1") (pintype "passive"))
      (node (ref "R10") (pin "2") (pinfunction "2_2") (pintype "passive"))
      (node (ref "R11") (pin "2") (pinfunction "2_2") (pintype "passive"))
      (node (ref "TP4") (pin "TP") (pinfunction "TP_TP") (pintype "input"))
      (node (ref "U2") (pin "4") (pinfunction "OUT_4") (pintype "output"))
    )
    (net (code "41") (name "S1_OUT_F") (class "Default")
      (node (ref "ADA4528") (pin "3") (pinfunction "INA+_3") (pintype "input"))
      (node (ref "C3") (pin "1") (pinfunction "1_1") (pintype "passive"))
      (node (ref "R11") (pin "1") (pinfunction "1_1") (pintype "passive"))
      (node (ref "TP5") (pin "TP") (pinfunction "TP_TP") (pintype "input"))
    )
    (net (code "42") (name "S2_OUT") (class "Default")
      (node (ref "ADA4528") (pin "1") (pinfunction "OUTA_1") (pintype "output"))
      (node (ref "C6") (pin "1") (pinfunction "1_1") (pintype "passive"))
      (node (ref "R1") (pin "2") (pinfunction "2_2") (pintype "passive"))
      (node (ref "R12") (pin "2") (pinfunction "2_2") (pintype "passive"))
      (node (ref "R2") (pin "2") (pinfunction "2_2") (pintype "passive"))
      (node (ref "TP6") (pin "TP") (pinfunction "TP_TP") (pintype "input"))
    )
    (net (code "43") (name "SCL") (class "Default")
      (node (ref "INA226") (pin "5") (pinfunction "SCL_5") (pintype "input"))
      (node (ref "JP2") (pin "2") (pinfunction "2_2") (pintype "passive"))
      (node (ref "R40") (pin "1") (pinfunction "1_1") (pintype "passive"))
    )
    (net (code "44") (name "SDA") (class "Default")
      (node (ref "INA226") (pin "4") (pinfunction "SDA_4") (pintype "bidirectional"))
      (node (ref "JP2") (pin "3") (pinfunction "3_3") (pintype "passive"))
      (node (ref "R39") (pin "1") (pinfunction "1_1") (pintype "passive"))
    )
    (net (code "45") (name "SHUNT_V+") (class "Default")
      (node (ref "INA226") (pin "8") (pinfunction "VBUS_8") (pintype "input"))
      (node (ref "R21") (pin "1") (pinfunction "1_1") (pintype "passive"))
      (node (ref "R8") (pin "1") (pinfunction "1_1") (pintype "passive"))
      (node (ref "TP9") (pin "TP") (pinfunction "TP_TP") (pintype "input"))
      (node (ref "U$1") (pin "I1") (pinfunction "I1_I1") (pintype "bidirectional"))
    )
    (net (code "46") (name "SHUNT_V-") (class "Default")
      (node (ref "R22") (pin "1") (pinfunction "1_1") (pintype "passive"))
      (node (ref "R6") (pin "1") (pinfunction "1_1") (pintype "passive"))
      (node (ref "TP10") (pin "TP") (pinfunction "TP_TP") (pintype "input"))
      (node (ref "U$1") (pin "I2") (pinfunction "I2_I2") (pintype "bidirectional"))
    )
    (net (code "47") (name "SW_CTRL_0") (class "Default")
      (node (ref "JP1") (pin "1") (pinfunction "1_1") (pintype "passive"))
      (node (ref "R33") (pin "2") (pinfunction "2_2") (pintype "passive"))
      (node (ref "TS5A3159") (pin "6") (pinfunction "IN_6") (pintype "input"))
    )
    (net (code "48") (name "SW_CTRL_1") (class "Default")
      (node (ref "JP3") (pin "1") (pinfunction "1_1") (pintype "passive"))
      (node (ref "R34") (pin "2") (pinfunction "2_2") (pintype "passive"))
      (node (ref "TS5A23166_1") (pin "1") (pinfunction "NO1_1") (pintype "passive"))
    )
    (net (code "49") (name "SW_CTRL_2") (class "Default")
      (node (ref "JP3") (pin "2") (pinfunction "2_2") (pintype "passive"))
      (node (ref "R35") (pin "2") (pinfunction "2_2") (pintype "passive"))
      (node (ref "TS5A23166_1") (pin "5") (pinfunction "NO2_5") (pintype "passive"))
    )
    (net (code "50") (name "SW_CTRL_3") (class "Default")
      (node (ref "JP3") (pin "3") (pinfunction "3_3") (pintype "passive"))
      (node (ref "R36") (pin "2") (pinfunction "2_2") (pintype "passive"))
      (node (ref "TS5A23166_2") (pin "1") (pinfunction "NO1_1") (pintype "passive"))
    )
    (net (code "51") (name "SW_CTRL_4") (class "Default")
      (node (ref "JP3") (pin "4") (pinfunction "4_4") (pintype "passive"))
      (node (ref "R37") (pin "2") (pinfunction "2_2") (pintype "passive"))
      (node (ref "TS5A23166_2") (pin "5") (pinfunction "NO2_5") (pintype "passive"))
    )
    (net (code "52") (name "SW_CTRL_PWR") (class "Default")
      (node (ref "JP1") (pin "2") (pinfunction "2_2") (pintype "passive"))
      (node (ref "R38") (pin "2") (pinfunction "2_2") (pintype "passive"))
      (node (ref "TS5A4624") (pin "1") (pinfunction "IN_1") (pintype "input"))
    )
    (net (code "53") (name "VIN") (class "Default")
      (node (ref "TP7") (pin "TP") (pinfunction "TP_TP") (pintype "input"))
      (node (ref "TS5A4624") (pin "5") (pinfunction "COM_5") (pintype "passive"))
      (node (ref "U$1") (pin "E1") (pinfunction "E1_E1") (pintype "bidirectional"))
    )
    (net (code "54") (name "VMCU") (class "Default")
      (node (ref "JP5") (pin "1") (pinfunction "1_1") (pintype "passive"))
      (node (ref "TS5A3159") (pin "1") (pinfunction "NO_1") (pintype "output"))
      (node (ref "VMCU_LED") (pin "A") (pinfunction "A_A") (pintype "passive"))
      (node (ref "X1") (pin "1") (pinfunction "1_1") (pintype "passive"))
    )
    (net (code "55") (name "VOUT") (class "Default")
      (node (ref "TP8") (pin "TP") (pinfunction "TP_TP") (pintype "input"))
      (node (ref "TS5A3159") (pin "4") (pinfunction "COM_4") (pintype "passive"))
      (node (ref "U$1") (pin "E2") (pinfunction "E2_E2") (pintype "bidirectional"))
    )
    (net (code "56") (name "V_CALIB") (class "Default")
      (node (ref "TS5A23166_1") (pin "3") (pinfunction "IN2_3") (pintype "input"))
      (node (ref "TS5A23166_1") (pin "7") (pinfunction "IN1_7") (pintype "input"))
      (node (ref "TS5A23166_2") (pin "3") (pinfunction "IN2_3") (pintype "input"))
      (node (ref "TS5A23166_2") (pin "7") (pinfunction "IN1_7") (pintype "input"))
      (node (ref "TS5A3159") (pin "3") (pinfunction "NC_3") (pintype "passive"))
      (node (ref "VCALIB_LED") (pin "A") (pinfunction "A_A") (pintype "passive"))
    )
    (net (code "57") (name "V_EXT") (class "Default")
      (node (ref "JP6") (pin "3") (pinfunction "3_3") (pintype "passive"))
      (node (ref "TS5A4624") (pin "6") (pinfunction "NO_6") (pintype "output"))
      (node (ref "VMCU_EXT_LED") (pin "A") (pinfunction "A_A") (pintype "passive"))
    )
    (net (code "58") (name "unconnected-(J1-ID-Pad4)") (class "Default")
      (node (ref "J1") (pin "4") (pinfunction "ID_4") (pintype "passive"))
    )
  )
)
